# Copy_of_Audio_input_ADC.net
KiCad netlist of a schematic drawn in Altium Designer
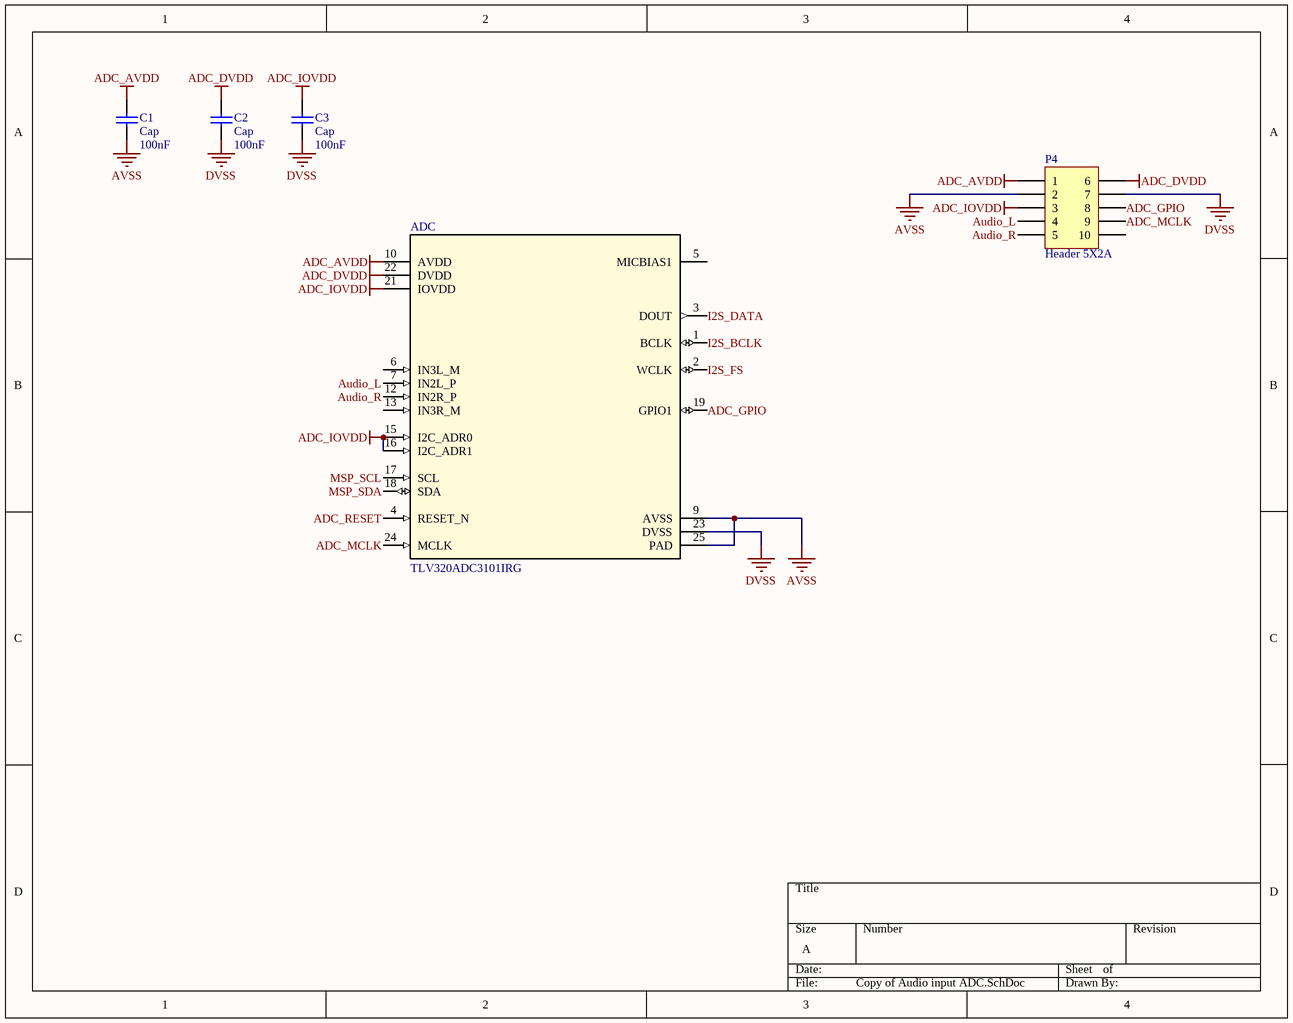
[diagram p0: Copy of Audio input ADC.SchDoc]

(export (version "E")
  (design (tool "Eeschema 10.0.6"))
  (components
    (comp (ref "ADC")
      (value "TLV320ADC3101IRG")
      (footprint "RGE0024F_NV")
      (description "Imported")
      (fields
        (field (name "MANUFACTURER") "Texas Instruments")
        (field (name "PARTNUMBER") "TLV320ADC3101IRGER")
      )
      (libsource (lib "2018-10-01_18-58-29") (part "TLV320ADC3101IRG"))
    )
    (comp (ref "C1")
      (value "Cap")
      (footprint "RAD-0.3")
      (description "Capacitor")
      (fields (field (name "ALTIUM_VALUE") "100nF") (field (name "PUBLISHER") "Altium Limited"))
      (libsource (lib "Miscellaneous Devices") (part "Cap"))
    )
    (comp (ref "C2")
      (value "Cap")
      (footprint "RAD-0.3")
      (description "Capacitor")
      (fields (field (name "ALTIUM_VALUE") "100nF") (field (name "PUBLISHER") "Altium Limited"))
      (libsource (lib "Miscellaneous Devices") (part "Cap"))
    )
    (comp (ref "C3")
      (value "Cap")
      (footprint "RAD-0.3")
      (description "Capacitor")
      (fields (field (name "ALTIUM_VALUE") "100nF") (field (name "PUBLISHER") "Altium Limited"))
      (libsource (lib "Miscellaneous Devices") (part "Cap"))
    )
    (comp (ref "P4")
      (value "Header 5X2A")
      (footprint "HDR2X5_CEN")
      (description "Header, 5-Pin, Dual row")
      (fields (field (name "PUBLISHER") "Altium Limited"))
      (libsource (lib "Miscellaneous Connectors") (part "Header 5X2A"))
    )
  )
  (nets
    (net (code "1") (name "/ADC_GPIO") (class "Default")
      (node (ref "ADC") (pin "19") (pinfunction "GPIO1_19") (pintype "bidirectional"))
      (node (ref "P4") (pin "8") (pinfunction "8_8") (pintype "passive"))
    )
    (net (code "2") (name "/ADC_MCLK") (class "Default")
      (node (ref "ADC") (pin "24") (pinfunction "MCLK_24") (pintype "input"))
      (node (ref "P4") (pin "9") (pinfunction "9_9") (pintype "passive"))
    )
    (net (code "3") (name "/ADC_RESET") (class "Default")
      (node (ref "ADC") (pin "4") (pinfunction "RESET_N_4") (pintype "input"))
    )
    (net (code "4") (name "/Audio_L") (class "Default")
      (node (ref "ADC") (pin "7") (pinfunction "IN2L_P_7") (pintype "input"))
      (node (ref "P4") (pin "4") (pinfunction "4_4") (pintype "passive"))
    )
    (net (code "5") (name "/Audio_R") (class "Default")
      (node (ref "ADC") (pin "12") (pinfunction "IN2R_P_12") (pintype "input"))
      (node (ref "P4") (pin "5") (pinfunction "5_5") (pintype "passive"))
    )
    (net (code "6") (name "/I2S_BCLK") (class "Default")
      (node (ref "ADC") (pin "1") (pinfunction "BCLK_1") (pintype "bidirectional"))
    )
    (net (code "7") (name "/I2S_DATA") (class "Default")
      (node (ref "ADC") (pin "3") (pinfunction "DOUT_3") (pintype "output"))
    )
    (net (code "8") (name "/I2S_FS") (class "Default")
      (node (ref "ADC") (pin "2") (pinfunction "WCLK_2") (pintype "bidirectional"))
    )
    (net (code "9") (name "/MSP_SCL") (class "Default")
      (node (ref "ADC") (pin "17") (pinfunction "SCL_17") (pintype "input"))
    )
    (net (code "10") (name "/MSP_SDA") (class "Default")
      (node (ref "ADC") (pin "18") (pinfunction "SDA_18") (pintype "bidirectional"))
    )
    (net (code "11") (name "ADC_AVDD") (class "Default")
      (node (ref "ADC") (pin "10") (pinfunction "AVDD_10") (pintype "power_in"))
      (node (ref "C1") (pin "2") (pinfunction "2_2") (pintype "passive"))
      (node (ref "P4") (pin "1") (pinfunction "1_1") (pintype "passive"))
    )
    (net (code "12") (name "ADC_DVDD") (class "Default")
      (node (ref "ADC") (pin "22") (pinfunction "DVDD_22") (pintype "power_in"))
      (node (ref "C2") (pin "2") (pinfunction "2_2") (pintype "passive"))
      (node (ref "P4") (pin "6") (pinfunction "6_6") (pintype "passive"))
    )
    (net (code "13") (name "ADC_IOVDD") (class "Default")
      (node (ref "ADC") (pin "15") (pinfunction "I2C_ADR0_15") (pintype "input"))
      (node (ref "ADC") (pin "16") (pinfunction "I2C_ADR1_16") (pintype "input"))
      (node (ref "ADC") (pin "21") (pinfunction "IOVDD_21") (pintype "power_in"))
      (node (ref "C3") (pin "2") (pinfunction "2_2") (pintype "passive"))
      (node (ref "P4") (pin "3") (pinfunction "3_3") (pintype "passive"))
    )
    (net (code "14") (name "AVSS") (class "Default")
      (node (ref "ADC") (pin "25") (pinfunction "PAD_25") (pintype "power_in"))
      (node (ref "ADC") (pin "9") (pinfunction "AVSS_9") (pintype "power_in"))
      (node (ref "C1") (pin "1") (pinfunction "1_1") (pintype "passive"))
      (node (ref "P4") (pin "2") (pinfunction "2_2") (pintype "passive"))
    )
    (net (code "15") (name "DVSS") (class "Default")
      (node (ref "ADC") (pin "23") (pinfunction "DVSS_23") (pintype "power_in"))
      (node (ref "C2") (pin "1") (pinfunction "1_1") (pintype "passive"))
      (node (ref "C3") (pin "1") (pinfunction "1_1") (pintype "passive"))
      (node (ref "P4") (pin "7") (pinfunction "7_7") (pintype "passive"))
    )
    (net (code "16") (name "unconnected-(ADC-IN3L_M-Pad6)") (class "Default")
      (node (ref "ADC") (pin "6") (pinfunction "IN3L_M_6") (pintype "input"))
    )
    (net (code "17") (name "unconnected-(ADC-IN3R_M-Pad13)") (class "Default")
      (node (ref "ADC") (pin "13") (pinfunction "IN3R_M_13") (pintype "input"))
    )
    (net (code "18") (name "unconnected-(ADC-MICBIAS1-Pad5)") (class "Default")
      (node (ref "ADC") (pin "5") (pinfunction "MICBIAS1_5") (pintype "power_in"))
    )
    (net (code "19") (name "unconnected-(P4-Pad10)") (class "Default")
      (node (ref "P4") (pin "10") (pinfunction "10_10") (pintype "passive"))
    )
  )
)
